# Veroboard_for_ckt_designing.net
KiCad netlist of a schematic drawn in EAGLE
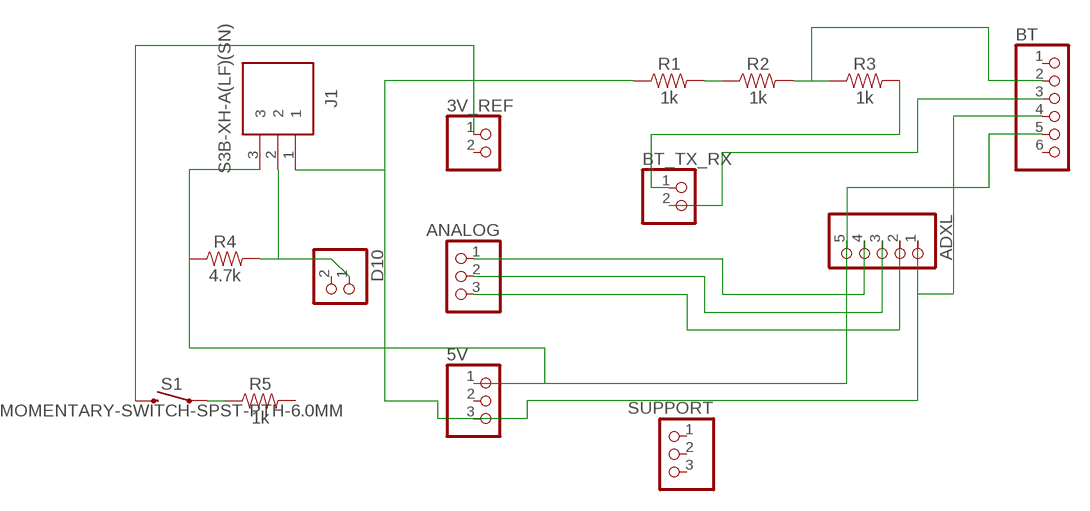
[diagram p0: schematic, sheet 2]

(export (version "E")
  (design (tool "Eeschema 10.0.6"))
  (components
    (comp (ref "3V_REF")
      (value "PINHD-1X2")
      (footprint "eagle-import:1X02")
      (libsource (lib "eagle-import") (part "PINHD-1X2"))
    )
    (comp (ref "5V")
      (value "PINHD-1X3")
      (footprint "eagle-import:1X03")
      (libsource (lib "eagle-import") (part "PINHD-1X3"))
    )
    (comp (ref "ADXL")
      (value "PINHD-1X5")
      (footprint "eagle-import:1X05")
      (libsource (lib "eagle-import") (part "PINHD-1X5"))
    )
    (comp (ref "ANALOG")
      (value "PINHD-1X3")
      (footprint "eagle-import:1X03")
      (libsource (lib "eagle-import") (part "PINHD-1X3"))
    )
    (comp (ref "BT")
      (value "PINHD-1X6")
      (footprint "eagle-import:1X06")
      (libsource (lib "eagle-import") (part "PINHD-1X6"))
    )
    (comp (ref "BT_TX_RX")
      (value "PINHD-1X2")
      (footprint "eagle-import:1X02")
      (libsource (lib "eagle-import") (part "PINHD-1X2"))
    )
    (comp (ref "D10")
      (value "PINHD-1X2")
      (footprint "eagle-import:1X02")
      (libsource (lib "eagle-import") (part "PINHD-1X2"))
    )
    (comp (ref "J1")
      (value "S3B-XH-A(LF)(SN)")
      (footprint "eagle-import:SHDR3W80P0X250_1X3_990X610X700")
      (fields (field (name "RS_PART_NUMBER") "8201585"))
      (libsource (lib "eagle-import") (part "S3B-XH-A(LF)(SN)"))
    )
    (comp (ref "R1")
      (value "1k")
      (footprint "eagle-import:AXIAL-0.3")
      (libsource (lib "eagle-import") (part "1KOHM-HORIZ-1/4W-1%"))
    )
    (comp (ref "R2")
      (value "1k")
      (footprint "eagle-import:AXIAL-0.3")
      (libsource (lib "eagle-import") (part "1KOHM-HORIZ-1/4W-1%"))
    )
    (comp (ref "R3")
      (value "1k")
      (footprint "eagle-import:AXIAL-0.3")
      (libsource (lib "eagle-import") (part "1KOHM-HORIZ-1/4W-1%"))
    )
    (comp (ref "R4")
      (value "4.7k")
      (footprint "eagle-import:AXIAL-0.3")
      (libsource (lib "eagle-import") (part "1KOHM-HORIZ-1/4W-1%"))
    )
    (comp (ref "R5")
      (value "1k")
      (footprint "eagle-import:AXIAL-0.3")
      (libsource (lib "eagle-import") (part "1KOHM-HORIZ-1/4W-1%"))
    )
    (comp (ref "S1")
      (value "MOMENTARY-SWITCH-SPST-PTH-6.0MM")
      (footprint "eagle-import:TACTILE_SWITCH_PTH_6.0MM")
      (libsource (lib "eagle-import") (part "MOMENTARY-SWITCH-SPST-PTH-6.0MM"))
    )
    (comp (ref "SUPPORT")
      (value "PINHD-1X3")
      (footprint "eagle-import:1X03")
      (libsource (lib "eagle-import") (part "PINHD-1X3"))
    )
  )
  (nets
    (net (code "1") (name "Net-(ADXL-Pad2)") (class "Default")
      (node (ref "ADXL") (pin "2") (pinfunction "2_2") (pintype "passive"))
      (node (ref "ANALOG") (pin "3") (pinfunction "3_3") (pintype "passive"))
    )
    (net (code "2") (name "Net-(ADXL-Pad3)") (class "Default")
      (node (ref "ADXL") (pin "3") (pinfunction "3_3") (pintype "passive"))
      (node (ref "ANALOG") (pin "2") (pinfunction "2_2") (pintype "passive"))
    )
    (net (code "3") (name "Net-(ADXL-Pad4)") (class "Default")
      (node (ref "ADXL") (pin "4") (pinfunction "4_4") (pintype "passive"))
      (node (ref "ANALOG") (pin "1") (pinfunction "1_1") (pintype "passive"))
    )
    (net (code "4") (name "Net-(BT-Pad3)") (class "Default")
      (node (ref "BT") (pin "3") (pinfunction "3_3") (pintype "passive"))
      (node (ref "BT_TX_RX") (pin "2") (pinfunction "2_2") (pintype "passive"))
    )
    (net (code "5") (name "Net-(R1-1)") (class "Default")
      (node (ref "5V") (pin "3") (pinfunction "3_3") (pintype "passive"))
      (node (ref "ADXL") (pin "1") (pinfunction "1_1") (pintype "passive"))
      (node (ref "BT") (pin "4") (pinfunction "4_4") (pintype "passive"))
      (node (ref "J1") (pin "1") (pinfunction "1_1") (pintype "passive"))
      (node (ref "R1") (pin "P$1") (pinfunction "1_P$1") (pintype "passive"))
    )
    (net (code "6") (name "Net-(R1-2)") (class "Default")
      (node (ref "R1") (pin "P$2") (pinfunction "2_P$2") (pintype "passive"))
      (node (ref "R2") (pin "P$1") (pinfunction "1_P$1") (pintype "passive"))
    )
    (net (code "7") (name "Net-(R2-2)") (class "Default")
      (node (ref "BT") (pin "2") (pinfunction "2_2") (pintype "passive"))
      (node (ref "R2") (pin "P$2") (pinfunction "2_P$2") (pintype "passive"))
      (node (ref "R3") (pin "P$1") (pinfunction "1_P$1") (pintype "passive"))
    )
    (net (code "8") (name "Net-(R3-2)") (class "Default")
      (node (ref "BT_TX_RX") (pin "1") (pinfunction "1_1") (pintype "passive"))
      (node (ref "R3") (pin "P$2") (pinfunction "2_P$2") (pintype "passive"))
    )
    (net (code "9") (name "Net-(R4-1)") (class "Default")
      (node (ref "5V") (pin "1") (pinfunction "1_1") (pintype "passive"))
      (node (ref "ADXL") (pin "5") (pinfunction "5_5") (pintype "passive"))
      (node (ref "BT") (pin "5") (pinfunction "5_5") (pintype "passive"))
      (node (ref "J1") (pin "3") (pinfunction "3_3") (pintype "passive"))
      (node (ref "R4") (pin "P$1") (pinfunction "1_P$1") (pintype "passive"))
    )
    (net (code "10") (name "Net-(R4-2)") (class "Default")
      (node (ref "D10") (pin "1") (pinfunction "1_1") (pintype "passive"))
      (node (ref "J1") (pin "2") (pinfunction "2_2") (pintype "passive"))
      (node (ref "R4") (pin "P$2") (pinfunction "2_P$2") (pintype "passive"))
    )
    (net (code "11") (name "Net-(R5-1)") (class "Default")
      (node (ref "R5") (pin "P$1") (pinfunction "1_P$1") (pintype "passive"))
      (node (ref "S1") (pin "1") (pinfunction "1_1") (pintype "passive"))
    )
    (net (code "12") (name "Net-(S1-2)") (class "Default")
      (node (ref "3V_REF") (pin "1") (pinfunction "1_1") (pintype "passive"))
      (node (ref "S1") (pin "3") (pinfunction "2_3") (pintype "passive"))
    )
    (net (code "13") (name "unconnected-(3V_REF-Pad2)") (class "Default")
      (node (ref "3V_REF") (pin "2") (pinfunction "2_2") (pintype "passive"))
    )
    (net (code "14") (name "unconnected-(5V-Pad2)") (class "Default")
      (node (ref "5V") (pin "2") (pinfunction "2_2") (pintype "passive"))
    )
    (net (code "15") (name "unconnected-(BT-Pad1)") (class "Default")
      (node (ref "BT") (pin "1") (pinfunction "1_1") (pintype "passive"))
    )
    (net (code "16") (name "unconnected-(BT-Pad6)") (class "Default")
      (node (ref "BT") (pin "6") (pinfunction "6_6") (pintype "passive"))
    )
    (net (code "17") (name "unconnected-(D10-Pad2)") (class "Default")
      (node (ref "D10") (pin "2") (pinfunction "2_2") (pintype "passive"))
    )
    (net (code "18") (name "unconnected-(R5-2-PadP$2)") (class "Default")
      (node (ref "R5") (pin "P$2") (pinfunction "2_P$2") (pintype "passive"))
    )
    (net (code "19") (name "unconnected-(SUPPORT-Pad1)") (class "Default")
      (node (ref "SUPPORT") (pin "1") (pinfunction "1_1") (pintype "passive"))
    )
    (net (code "20") (name "unconnected-(SUPPORT-Pad2)") (class "Default")
      (node (ref "SUPPORT") (pin "2") (pinfunction "2_2") (pintype "passive"))
    )
    (net (code "21") (name "unconnected-(SUPPORT-Pad3)") (class "Default")
      (node (ref "SUPPORT") (pin "3") (pinfunction "3_3") (pintype "passive"))
    )
  )
)
